# Block_Diagram.net
KiCad netlist of a schematic drawn in Altium Designer
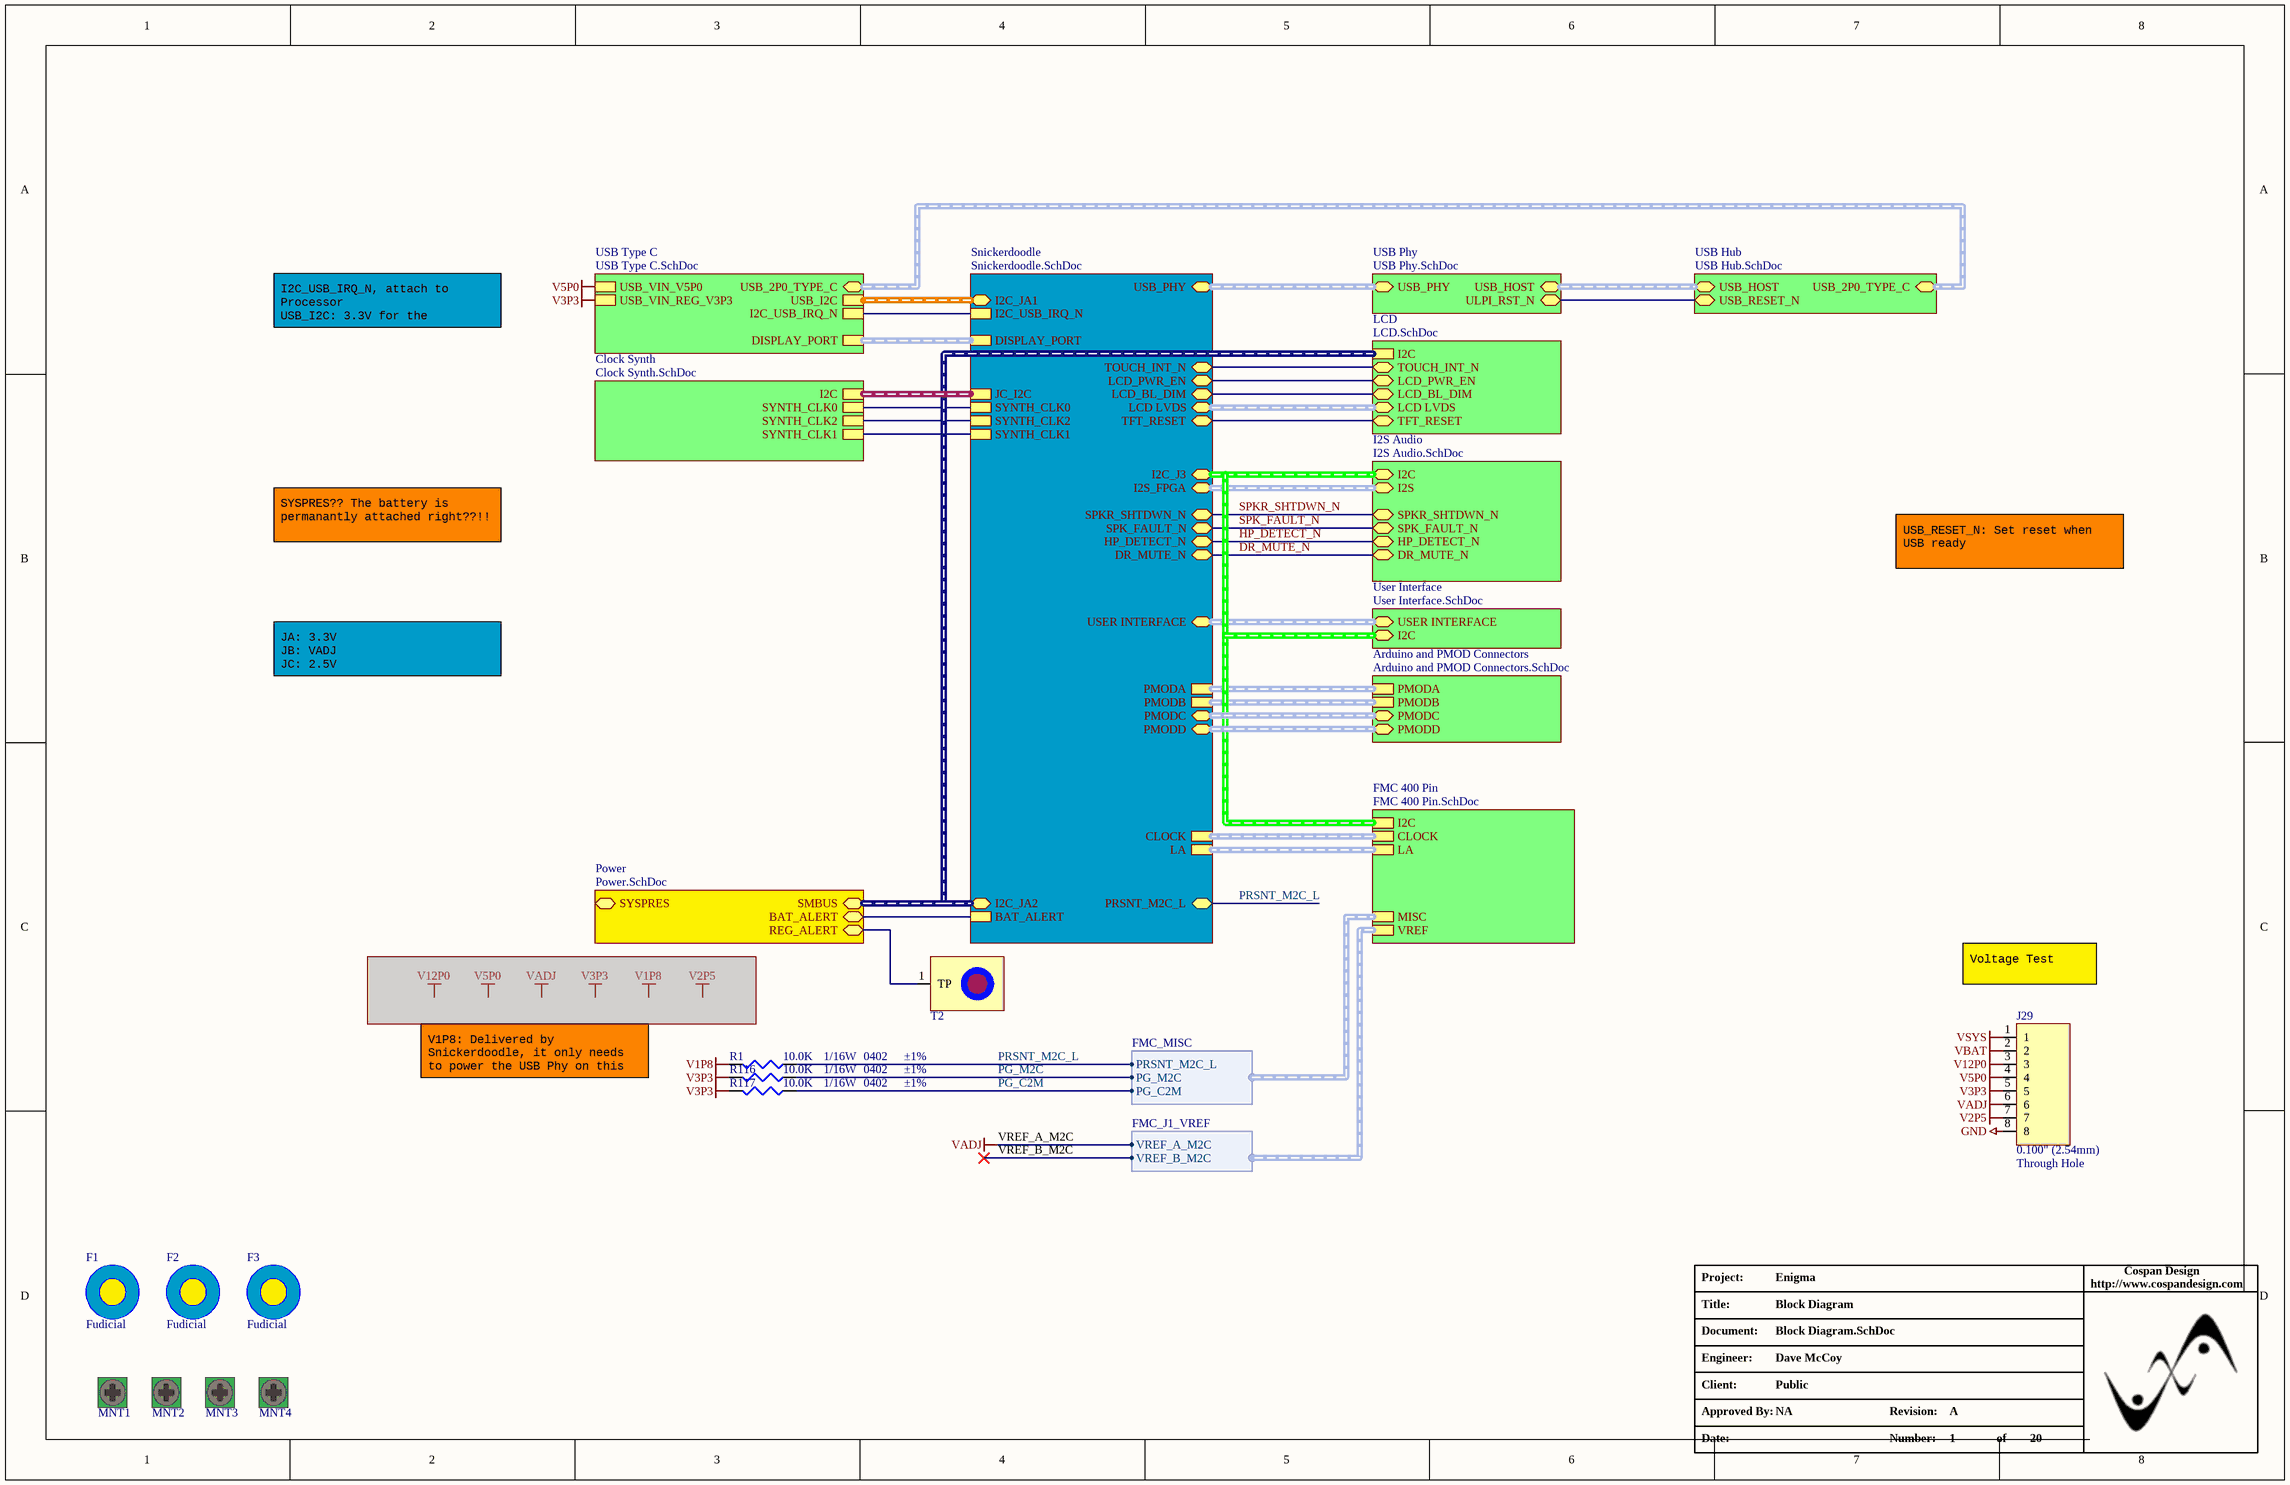
[diagram p0: Block Diagram.SchDoc]

(export (version "E")
  (design (tool "Eeschema 10.0.6"))
  (components
    (comp (ref "F1")
      (value "Fudicial")
      (footprint "FIDUCIAL ROUND")
      (libsource (lib "Main Library") (part "F_FUDICIAL"))
    )
    (comp (ref "F2")
      (value "Fudicial")
      (footprint "FIDUCIAL ROUND")
      (libsource (lib "Main Library") (part "F_FUDICIAL"))
    )
    (comp (ref "F3")
      (value "Fudicial")
      (footprint "FIDUCIAL ROUND")
      (libsource (lib "Main Library") (part "F_FUDICIAL"))
    )
    (comp (ref "J29")
      (value "J_HDR1X8_THRHOLE_VERT_RECPT")
      (footprint "HDR_1X8 - FEMALE")
      (description "CONN HEADER FEMALE 8POS .1\" TIN")
      (fields
        (field (name "MANUFACTURER") "Samtec")
        (field (name "MANUFACTURER PART NUMBER") "SSW-108-01-T-S")
        (field (name "PITCH") "0.100\" (2.54mm)")
        (field (name "MOUNTING TYPE") "Through Hole")
      )
      (libsource (lib "Main Library") (part "J_HDR1X8_THRHOLE_VERT_FEMALE"))
    )
    (comp (ref "MNT1")
      (value "Mounting Hole")
      (footprint "MNT_4-40")
      (libsource (lib "Main Library") (part "MNT_440_HOLE"))
    )
    (comp (ref "MNT2")
      (value "Mounting Hole")
      (footprint "MNT_4-40")
      (libsource (lib "Main Library") (part "MNT_440_HOLE"))
    )
    (comp (ref "MNT3")
      (value "Mounting Hole")
      (footprint "MNT_4-40")
      (libsource (lib "Main Library") (part "MNT_440_HOLE"))
    )
    (comp (ref "MNT4")
      (value "Mounting Hole")
      (footprint "MNT_4-40")
      (libsource (lib "Main Library") (part "MNT_440_HOLE"))
    )
    (comp (ref "R1")
      (value "R_0402_10.0K")
      (footprint "R_0402")
      (description "RES 10.0K OHM 1/16W 1% 0402 SMD")
      (fields
        (field (name "MANUFACTURER") "Stackpole Electronics Inc")
        (field (name "MANUFACTURER PART NUMBER") "RMCF0402FT10K0")
        (field (name "RESISTANCE IN OHMS") "10.0K")
        (field (name "POWER (WATTS)") "1/16W")
        (field (name "CASE") "0402")
        (field (name "TOLERANCE") "±1%")
      )
      (libsource (lib "Cospan Design") (part "R_0402_10.0K"))
    )
    (comp (ref "R116")
      (value "R_0402_10.0K")
      (footprint "R_0402")
      (description "RES 10.0K OHM 1/16W 1% 0402 SMD")
      (fields
        (field (name "MANUFACTURER") "Stackpole Electronics Inc")
        (field (name "MANUFACTURER PART NUMBER") "RMCF0402FT10K0")
        (field (name "RESISTANCE IN OHMS") "10.0K")
        (field (name "POWER (WATTS)") "1/16W")
        (field (name "CASE") "0402")
        (field (name "TOLERANCE") "±1%")
      )
      (libsource (lib "Cospan Design") (part "R_0402_10.0K"))
    )
    (comp (ref "R117")
      (value "R_0402_10.0K")
      (footprint "R_0402")
      (description "RES 10.0K OHM 1/16W 1% 0402 SMD")
      (fields
        (field (name "MANUFACTURER") "Stackpole Electronics Inc")
        (field (name "MANUFACTURER PART NUMBER") "RMCF0402FT10K0")
        (field (name "RESISTANCE IN OHMS") "10.0K")
        (field (name "POWER (WATTS)") "1/16W")
        (field (name "CASE") "0402")
        (field (name "TOLERANCE") "±1%")
      )
      (libsource (lib "Cospan Design") (part "R_0402_10.0K"))
    )
    (comp (ref "T2")
      (value "TEST_POINT_SMALL")
      (footprint "TestPointSmall")
      (description "OSCILLOSCOPE TEST POINT")
      (libsource (lib "Main Library") (part "TEST_POINT_SMALL"))
    )
  )
  (nets
    (net (code "18") (name "/PG_C2M") (class "Default")
      (node (ref "R117") (pin "2") (pinfunction "2_2") (pintype "passive"))
    )
    (net (code "19") (name "/PG_M2C") (class "Default")
      (node (ref "R116") (pin "2") (pinfunction "2_2") (pintype "passive"))
    )
    (net (code "24") (name "/PRSNT_M2C_L") (class "Default")
      (node (ref "R1") (pin "2") (pinfunction "2_2") (pintype "passive"))
    )
    (net (code "25") (name "/REG_ALERT") (class "Default")
      (node (ref "T2") (pin "1") (pinfunction "TP_1") (pintype "passive"))
    )
    (net (code "42") (name "GND") (class "Default")
      (node (ref "J29") (pin "8") (pinfunction "8_8") (pintype "passive"))
    )
    (net (code "43") (name "V1P8") (class "Default")
      (node (ref "R1") (pin "1") (pinfunction "1_1") (pintype "passive"))
    )
    (net (code "44") (name "V2P5") (class "Default")
      (node (ref "J29") (pin "7") (pinfunction "7_7") (pintype "passive"))
    )
    (net (code "45") (name "V3P3") (class "Default")
      (node (ref "J29") (pin "5") (pinfunction "5_5") (pintype "passive"))
      (node (ref "R116") (pin "1") (pinfunction "1_1") (pintype "passive"))
      (node (ref "R117") (pin "1") (pinfunction "1_1") (pintype "passive"))
    )
    (net (code "46") (name "V5P0") (class "Default")
      (node (ref "J29") (pin "4") (pinfunction "4_4") (pintype "passive"))
    )
    (net (code "47") (name "V12P0") (class "Default")
      (node (ref "J29") (pin "3") (pinfunction "3_3") (pintype "passive"))
    )
    (net (code "48") (name "VADJ") (class "Default")
      (node (ref "J29") (pin "6") (pinfunction "6_6") (pintype "passive"))
    )
    (net (code "49") (name "VBAT") (class "Default")
      (node (ref "J29") (pin "2") (pinfunction "2_2") (pintype "passive"))
    )
    (net (code "50") (name "VSYS") (class "Default")
      (node (ref "J29") (pin "1") (pinfunction "1_1") (pintype "passive"))
    )
  )
)
